# QSFP.net
KiCad netlist of a schematic drawn in Altium Designer
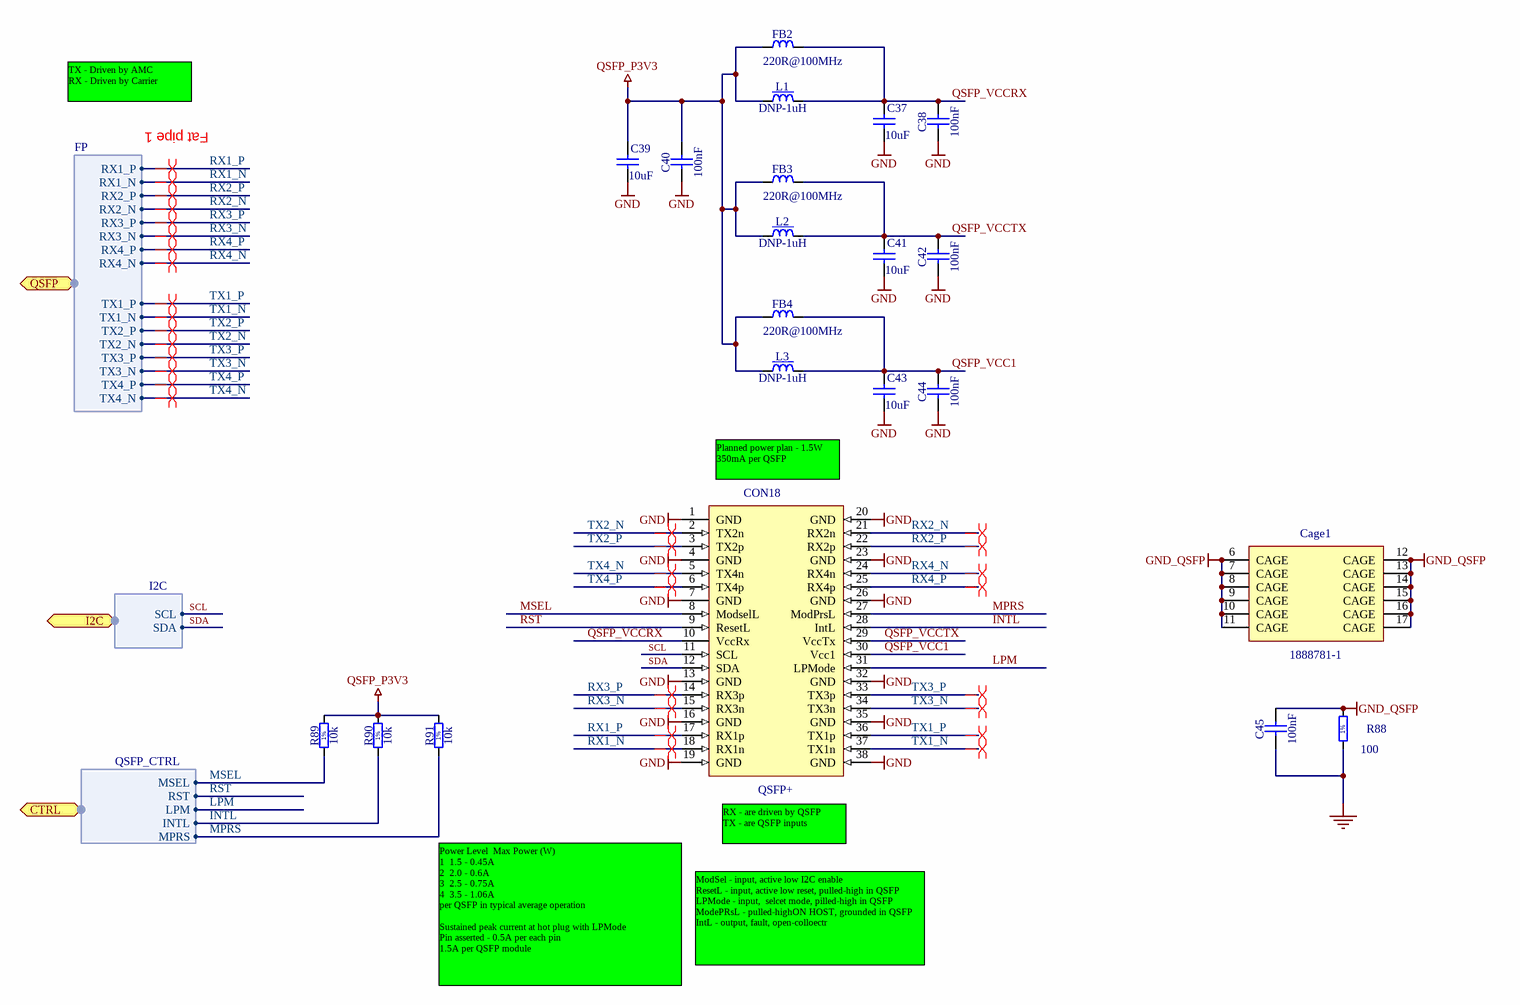
[diagram p0: QSFP.SchDoc]

(export (version "E")
  (design (tool "Eeschema 10.0.6"))
  (components
    (comp (ref "C37")
      (value "10uF")
      (footprint "CAPC2012X135N")
      (description "Non-polarised capacitor")
      (fields
        (field (name "PART NUMBER") "CC0805_10UF_10V_10%_X7R")
        (field (name "VOLTAGE") "10V")
        (field (name "AUTHOR") "CERN DEM JLC")
      )
      (libsource (lib "Capacitors") (part "Capacitor - non polarized"))
    )
    (comp (ref "C38")
      (value "100nF")
      (footprint "CAPC1005X55N")
      (description "Non-polarised capacitor")
      (fields
        (field (name "PART NUMBER") "CC0402_100NF_16V_10%_X5R")
        (field (name "VOLTAGE") "16V")
        (field (name "AUTHOR") "CERN DEM JLC")
      )
      (libsource (lib "Capacitors") (part "Capacitor - non polarized"))
    )
    (comp (ref "C39")
      (value "10uF")
      (footprint "CAPC2012X135N")
      (description "Non-polarised capacitor")
      (fields
        (field (name "PART NUMBER") "CC0805_10UF_10V_10%_X7R")
        (field (name "VOLTAGE") "10V")
        (field (name "AUTHOR") "CERN DEM JLC")
      )
      (libsource (lib "Capacitors") (part "Capacitor - non polarized"))
    )
    (comp (ref "C40")
      (value "100nF")
      (footprint "CAPC1005X55N")
      (description "Non-polarised capacitor")
      (fields
        (field (name "PART NUMBER") "CC0402_100NF_16V_10%_X5R")
        (field (name "VOLTAGE") "16V")
        (field (name "AUTHOR") "CERN DEM JLC")
      )
      (libsource (lib "Capacitors") (part "Capacitor - non polarized"))
    )
    (comp (ref "C41")
      (value "10uF")
      (footprint "CAPC2012X135N")
      (description "Non-polarised capacitor")
      (fields
        (field (name "PART NUMBER") "CC0805_10UF_10V_10%_X7R")
        (field (name "VOLTAGE") "10V")
        (field (name "AUTHOR") "CERN DEM JLC")
      )
      (libsource (lib "Capacitors") (part "Capacitor - non polarized"))
    )
    (comp (ref "C42")
      (value "100nF")
      (footprint "CAPC1005X55N")
      (description "Non-polarised capacitor")
      (fields
        (field (name "PART NUMBER") "CC0402_100NF_16V_10%_X5R")
        (field (name "VOLTAGE") "16V")
        (field (name "AUTHOR") "CERN DEM JLC")
      )
      (libsource (lib "Capacitors") (part "Capacitor - non polarized"))
    )
    (comp (ref "C43")
      (value "10uF")
      (footprint "CAPC2012X135N")
      (description "Non-polarised capacitor")
      (fields
        (field (name "PART NUMBER") "CC0805_10UF_10V_10%_X7R")
        (field (name "VOLTAGE") "10V")
        (field (name "AUTHOR") "CERN DEM JLC")
      )
      (libsource (lib "Capacitors") (part "Capacitor - non polarized"))
    )
    (comp (ref "C44")
      (value "100nF")
      (footprint "CAPC1005X55N")
      (description "Non-polarised capacitor")
      (fields
        (field (name "PART NUMBER") "CC0402_100NF_16V_10%_X5R")
        (field (name "VOLTAGE") "16V")
        (field (name "AUTHOR") "CERN DEM JLC")
      )
      (libsource (lib "Capacitors") (part "Capacitor - non polarized"))
    )
    (comp (ref "C45")
      (value "100nF")
      (footprint "CAPC1005X55N")
      (description "Non-polarised capacitor")
      (fields
        (field (name "PART NUMBER") "CC0402_100NF_16V_10%_X5R")
        (field (name "VOLTAGE") "16V")
        (field (name "AUTHOR") "CERN DEM JLC")
      )
      (libsource (lib "Capacitors") (part "Capacitor - non polarized"))
    )
    (comp (ref "Cage1")
      (value "1888781-1")
      (footprint "TYCO_1888781-1")
      (description "QSFP+ 1x3 Cage (23Pins)")
      (fields
        (field (name "PART NUMBER") "TYCO_2007456-1")
        (field (name "MANUFACTURER") "TYCO ELECTRONICS")
        (field (name "AUTHOR") "CERN DEM JLC")
      )
      (libsource (lib "LIBRARY_SCH") (part "CON_QSFP+_cage"))
    )
    (comp (ref "CON18")
      (value "QSFP+")
      (footprint "TYCO_1761987-9")
      (description "38Position QSFP Connector  (Quad Small Form-factor Pluggable)")
      (fields
        (field (name "PART NUMBER") "TYCO_1761987-9")
        (field (name "MANUFACTURER") "TYCO ELECTRONICS")
        (field (name "AUTHOR") "CERN DEM JLC")
      )
      (libsource (lib "Connectors") (part "QSFP+x1"))
    )
    (comp (ref "FB2")
      (value "220R@100MHz")
      (footprint "INDC2012X105N")
      (description "Inductor")
      (fields
        (field (name "PART NUMBER") "IND0805_MURATA_BLM21PG221SN1D")
        (field (name "POWER") "2A")
        (field (name "AUTHOR") "CERN DEM JLC")
      )
      (libsource (lib "Inductors & Transformers") (part "Inductor"))
    )
    (comp (ref "FB3")
      (value "220R@100MHz")
      (footprint "INDC2012X105N")
      (description "Inductor")
      (fields
        (field (name "PART NUMBER") "IND0805_MURATA_BLM21PG221SN1D")
        (field (name "POWER") "2A")
        (field (name "AUTHOR") "CERN DEM JLC")
      )
      (libsource (lib "Inductors & Transformers") (part "Inductor"))
    )
    (comp (ref "FB4")
      (value "220R@100MHz")
      (footprint "INDC2012X105N")
      (description "Inductor")
      (fields
        (field (name "PART NUMBER") "IND0805_MURATA_BLM21PG221SN1D")
        (field (name "POWER") "2A")
        (field (name "AUTHOR") "CERN DEM JLC")
      )
      (libsource (lib "Inductors & Transformers") (part "Inductor"))
    )
    (comp (ref "L1")
      (value "DNP-1uH")
      (footprint "IND_MURATA_LQH32")
      (description "Inductor With Magnetic core")
      (fields
        (field (name "PART NUMBER") "IND_1UH_20%_MURATA_LQH32CN1R0M33")
        (field (name "POWER") "1A")
        (field (name "AUTHOR") "CERN DEM JLC")
      )
      (libsource (lib "Inductors & Transformers") (part "Inductor With Magnetic core"))
    )
    (comp (ref "L2")
      (value "DNP-1uH")
      (footprint "IND_MURATA_LQH32")
      (description "Inductor With Magnetic core")
      (fields
        (field (name "PART NUMBER") "IND_1UH_20%_MURATA_LQH32CN1R0M33")
        (field (name "POWER") "1A")
        (field (name "AUTHOR") "CERN DEM JLC")
      )
      (libsource (lib "Inductors & Transformers") (part "Inductor With Magnetic core"))
    )
    (comp (ref "L3")
      (value "DNP-1uH")
      (footprint "IND_MURATA_LQH32")
      (description "Inductor With Magnetic core")
      (fields
        (field (name "PART NUMBER") "IND_1UH_20%_MURATA_LQH32CN1R0M33")
        (field (name "POWER") "1A")
        (field (name "AUTHOR") "CERN DEM JLC")
      )
      (libsource (lib "Inductors & Transformers") (part "Inductor With Magnetic core"))
    )
    (comp (ref "R88")
      (value "100")
      (footprint "RESC1005X40N")
      (description "Resistor - 1%")
      (fields
        (field (name "PART NUMBER") "R0402_100R_1%_0.0625W_100PPM")
        (field (name "POWER") "0.0625W")
        (field (name "AUTHOR") "CERN DEM JLC")
      )
      (libsource (lib "Resistors") (part "Resistor - 1%"))
    )
    (comp (ref "R89")
      (value "10k")
      (footprint "RESC1005X40N")
      (description "Resistor - 1%")
      (fields
        (field (name "PART NUMBER") "R0402_10K_1%_0.0625W_100PPM")
        (field (name "POWER") "0.0625W")
        (field (name "AUTHOR") "CERN DEM JLC")
      )
      (libsource (lib "Resistors") (part "Resistor - 1%"))
    )
    (comp (ref "R90")
      (value "10k")
      (footprint "RESC1005X40N")
      (description "Resistor - 1%")
      (fields
        (field (name "PART NUMBER") "R0402_10K_1%_0.0625W_100PPM")
        (field (name "POWER") "0.0625W")
        (field (name "AUTHOR") "CERN DEM JLC")
      )
      (libsource (lib "Resistors") (part "Resistor - 1%"))
    )
    (comp (ref "R91")
      (value "10k")
      (footprint "RESC1005X40N")
      (description "Resistor - 1%")
      (fields
        (field (name "PART NUMBER") "R0402_10K_1%_0.0625W_100PPM")
        (field (name "POWER") "0.0625W")
        (field (name "AUTHOR") "CERN DEM JLC")
      )
      (libsource (lib "Resistors") (part "Resistor - 1%"))
    )
  )
  (nets
    (net (code "4") (name "/INTL") (class "Default")
      (node (ref "CON18") (pin "28") (pinfunction "IntL_28") (pintype "input"))
      (node (ref "R90") (pin "1") (pinfunction "1_1") (pintype "passive"))
    )
    (net (code "5") (name "/LPM") (class "Default")
      (node (ref "CON18") (pin "31") (pinfunction "LPMode_31") (pintype "input"))
    )
    (net (code "6") (name "/MPRS") (class "Default")
      (node (ref "CON18") (pin "27") (pinfunction "ModPrsL_27") (pintype "input"))
      (node (ref "R91") (pin "1") (pinfunction "1_1") (pintype "passive"))
    )
    (net (code "7") (name "/MSEL") (class "Default")
      (node (ref "CON18") (pin "8") (pinfunction "ModselL_8") (pintype "input"))
      (node (ref "R89") (pin "1") (pinfunction "1_1") (pintype "passive"))
    )
    (net (code "8") (name "/QSFP_VCC1") (class "Default")
      (node (ref "C43") (pin "1") (pinfunction "1_1") (pintype "passive"))
      (node (ref "C44") (pin "2") (pinfunction "2_2") (pintype "passive"))
      (node (ref "CON18") (pin "30") (pinfunction "Vcc1_30") (pintype "input"))
      (node (ref "FB4") (pin "2") (pinfunction "2_2") (pintype "passive"))
      (node (ref "L3") (pin "2") (pinfunction "2_2") (pintype "passive"))
    )
    (net (code "9") (name "/QSFP_VCCRX") (class "Default")
      (node (ref "C37") (pin "1") (pinfunction "1_1") (pintype "passive"))
      (node (ref "C38") (pin "2") (pinfunction "2_2") (pintype "passive"))
      (node (ref "CON18") (pin "10") (pinfunction "VccRx_10") (pintype "power_in"))
      (node (ref "FB2") (pin "2") (pinfunction "2_2") (pintype "passive"))
      (node (ref "L1") (pin "2") (pinfunction "2_2") (pintype "passive"))
    )
    (net (code "10") (name "/QSFP_VCCTX") (class "Default")
      (node (ref "C41") (pin "1") (pinfunction "1_1") (pintype "passive"))
      (node (ref "C42") (pin "2") (pinfunction "2_2") (pintype "passive"))
      (node (ref "CON18") (pin "29") (pinfunction "VccTx_29") (pintype "input"))
      (node (ref "FB3") (pin "2") (pinfunction "2_2") (pintype "passive"))
      (node (ref "L2") (pin "2") (pinfunction "2_2") (pintype "passive"))
    )
    (net (code "11") (name "/RST") (class "Default")
      (node (ref "CON18") (pin "9") (pinfunction "ResetL_9") (pintype "input"))
    )
    (net (code "12") (name "/RX1_N") (class "Default")
      (node (ref "CON18") (pin "18") (pinfunction "RX1n_18") (pintype "input"))
    )
    (net (code "13") (name "/RX1_P") (class "Default")
      (node (ref "CON18") (pin "17") (pinfunction "RX1p_17") (pintype "input"))
    )
    (net (code "14") (name "/RX2_N") (class "Default")
      (node (ref "CON18") (pin "21") (pinfunction "RX2n_21") (pintype "input"))
    )
    (net (code "15") (name "/RX2_P") (class "Default")
      (node (ref "CON18") (pin "22") (pinfunction "RX2p_22") (pintype "input"))
    )
    (net (code "16") (name "/RX3_N") (class "Default")
      (node (ref "CON18") (pin "15") (pinfunction "RX3n_15") (pintype "input"))
    )
    (net (code "17") (name "/RX3_P") (class "Default")
      (node (ref "CON18") (pin "14") (pinfunction "RX3p_14") (pintype "input"))
    )
    (net (code "18") (name "/RX4_N") (class "Default")
      (node (ref "CON18") (pin "24") (pinfunction "RX4n_24") (pintype "input"))
    )
    (net (code "19") (name "/RX4_P") (class "Default")
      (node (ref "CON18") (pin "25") (pinfunction "RX4p_25") (pintype "input"))
    )
    (net (code "20") (name "/SCL") (class "Default")
      (node (ref "CON18") (pin "11") (pinfunction "SCL_11") (pintype "input"))
    )
    (net (code "21") (name "/SDA") (class "Default")
      (node (ref "CON18") (pin "12") (pinfunction "SDA_12") (pintype "input"))
    )
    (net (code "22") (name "/TX1_N") (class "Default")
      (node (ref "CON18") (pin "37") (pinfunction "TX1n_37") (pintype "input"))
    )
    (net (code "23") (name "/TX1_P") (class "Default")
      (node (ref "CON18") (pin "36") (pinfunction "TX1p_36") (pintype "input"))
    )
    (net (code "24") (name "/TX2_N") (class "Default")
      (node (ref "CON18") (pin "2") (pinfunction "TX2n_2") (pintype "input"))
    )
    (net (code "25") (name "/TX2_P") (class "Default")
      (node (ref "CON18") (pin "3") (pinfunction "TX2p_3") (pintype "input"))
    )
    (net (code "26") (name "/TX3_N") (class "Default")
      (node (ref "CON18") (pin "34") (pinfunction "TX3n_34") (pintype "input"))
    )
    (net (code "27") (name "/TX3_P") (class "Default")
      (node (ref "CON18") (pin "33") (pinfunction "TX3p_33") (pintype "input"))
    )
    (net (code "28") (name "/TX4_N") (class "Default")
      (node (ref "CON18") (pin "5") (pinfunction "TX4n_5") (pintype "input"))
    )
    (net (code "29") (name "/TX4_P") (class "Default")
      (node (ref "CON18") (pin "6") (pinfunction "TX4p_6") (pintype "input"))
    )
    (net (code "33") (name "GND") (class "Default")
      (node (ref "C37") (pin "2") (pinfunction "2_2") (pintype "passive"))
      (node (ref "C38") (pin "1") (pinfunction "1_1") (pintype "passive"))
      (node (ref "C39") (pin "2") (pinfunction "2_2") (pintype "passive"))
      (node (ref "C40") (pin "1") (pinfunction "1_1") (pintype "passive"))
      (node (ref "C41") (pin "2") (pinfunction "2_2") (pintype "passive"))
      (node (ref "C42") (pin "1") (pinfunction "1_1") (pintype "passive"))
      (node (ref "C43") (pin "2") (pinfunction "2_2") (pintype "passive"))
      (node (ref "C44") (pin "1") (pinfunction "1_1") (pintype "passive"))
      (node (ref "C45") (pin "1") (pinfunction "1_1") (pintype "passive"))
      (node (ref "CON18") (pin "1") (pinfunction "GND_1") (pintype "power_in"))
      (node (ref "CON18") (pin "13") (pinfunction "GND_13") (pintype "input"))
      (node (ref "CON18") (pin "16") (pinfunction "GND_16") (pintype "input"))
      (node (ref "CON18") (pin "19") (pinfunction "GND_19") (pintype "input"))
      (node (ref "CON18") (pin "20") (pinfunction "GND_20") (pintype "input"))
      (node (ref "CON18") (pin "23") (pinfunction "GND_23") (pintype "input"))
      (node (ref "CON18") (pin "26") (pinfunction "GND_26") (pintype "input"))
      (node (ref "CON18") (pin "32") (pinfunction "GND_32") (pintype "input"))
      (node (ref "CON18") (pin "35") (pinfunction "GND_35") (pintype "input"))
      (node (ref "CON18") (pin "38") (pinfunction "GND_38") (pintype "input"))
      (node (ref "CON18") (pin "4") (pinfunction "GND_4") (pintype "power_in"))
      (node (ref "CON18") (pin "7") (pinfunction "GND_7") (pintype "power_in"))
      (node (ref "R88") (pin "1") (pinfunction "1_1") (pintype "passive"))
    )
    (net (code "34") (name "GND_QSFP") (class "Default")
      (node (ref "C45") (pin "2") (pinfunction "2_2") (pintype "passive"))
      (node (ref "Cage1") (pin "10") (pinfunction "CAGE_10") (pintype "power_in"))
      (node (ref "Cage1") (pin "11") (pinfunction "CAGE_11") (pintype "power_in"))
      (node (ref "Cage1") (pin "12") (pinfunction "CAGE_12") (pintype "power_in"))
      (node (ref "Cage1") (pin "13") (pinfunction "CAGE_13") (pintype "power_in"))
      (node (ref "Cage1") (pin "14") (pinfunction "CAGE_14") (pintype "power_in"))
      (node (ref "Cage1") (pin "15") (pinfunction "CAGE_15") (pintype "power_in"))
      (node (ref "Cage1") (pin "16") (pinfunction "CAGE_16") (pintype "power_in"))
      (node (ref "Cage1") (pin "17") (pinfunction "CAGE_17") (pintype "power_in"))
      (node (ref "Cage1") (pin "6") (pinfunction "CAGE_6") (pintype "power_in"))
      (node (ref "Cage1") (pin "7") (pinfunction "CAGE_7") (pintype "power_in"))
      (node (ref "Cage1") (pin "8") (pinfunction "CAGE_8") (pintype "power_in"))
      (node (ref "Cage1") (pin "9") (pinfunction "CAGE_9") (pintype "power_in"))
      (node (ref "R88") (pin "2") (pinfunction "2_2") (pintype "passive"))
    )
    (net (code "35") (name "QSFP_P3V3") (class "Default")
      (node (ref "C39") (pin "1") (pinfunction "1_1") (pintype "passive"))
      (node (ref "C40") (pin "2") (pinfunction "2_2") (pintype "passive"))
      (node (ref "FB2") (pin "1") (pinfunction "1_1") (pintype "passive"))
      (node (ref "FB3") (pin "1") (pinfunction "1_1") (pintype "passive"))
      (node (ref "FB4") (pin "1") (pinfunction "1_1") (pintype "passive"))
      (node (ref "L1") (pin "1") (pinfunction "1_1") (pintype "passive"))
      (node (ref "L2") (pin "1") (pinfunction "1_1") (pintype "passive"))
      (node (ref "L3") (pin "1") (pinfunction "1_1") (pintype "passive"))
      (node (ref "R89") (pin "2") (pinfunction "2_2") (pintype "passive"))
      (node (ref "R90") (pin "2") (pinfunction "2_2") (pintype "passive"))
      (node (ref "R91") (pin "2") (pinfunction "2_2") (pintype "passive"))
    )
  )
)
